# Light_Schematic.net
KiCad netlist of a schematic drawn in EAGLE
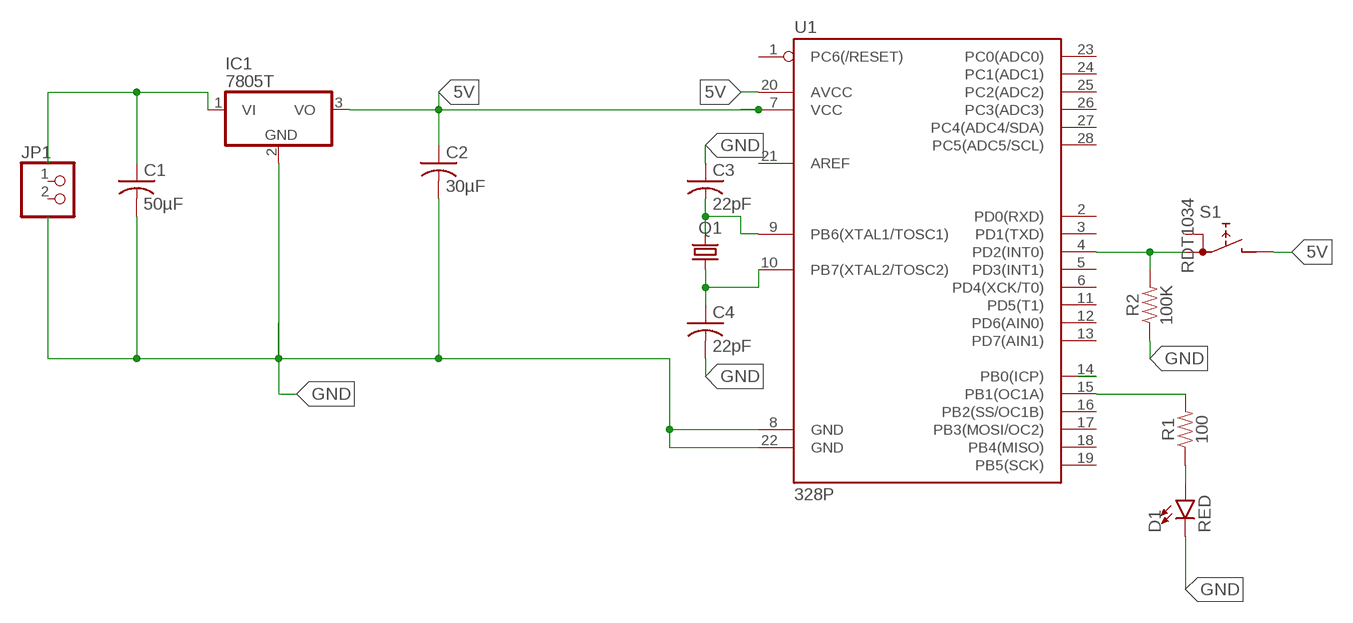
[diagram p0: schematic, sheet 1]

(export (version "E")
  (design (tool "Eeschema 10.0.6"))
  (components
    (comp (ref "C1")
      (value "50µF")
      (footprint "eagle-import:C0805")
      (libsource (lib "eagle-import") (part "C-USC0805"))
    )
    (comp (ref "C2")
      (value "30µF")
      (footprint "eagle-import:C0805")
      (libsource (lib "eagle-import") (part "C-USC0805"))
    )
    (comp (ref "C3")
      (value "22pF")
      (footprint "eagle-import:C0805")
      (libsource (lib "eagle-import") (part "C-USC0805"))
    )
    (comp (ref "C4")
      (value "22pF")
      (footprint "eagle-import:C0805")
      (libsource (lib "eagle-import") (part "C-USC0805"))
    )
    (comp (ref "D1")
      (value "RED")
      (footprint "eagle-import:LED-0603")
      (libsource (lib "eagle-import") (part "LED-RED0603"))
    )
    (comp (ref "IC1")
      (value "7805T")
      (footprint "eagle-import:TO220H")
      (libsource (lib "eagle-import") (part "78T05"))
    )
    (comp (ref "JP1")
      (value "PINHD-1X2")
      (footprint "eagle-import:1X02")
      (libsource (lib "eagle-import") (part "PINHD-1X2"))
    )
    (comp (ref "Q1")
      (value "CRYSTALHC49S")
      (footprint "eagle-import:HC49_S")
      (libsource (lib "eagle-import") (part "CRYSTALHC49S"))
    )
    (comp (ref "R1")
      (value "100")
      (footprint "eagle-import:0402")
      (libsource (lib "eagle-import") (part "100KOHM-0402-1/16W-1%"))
    )
    (comp (ref "R2")
      (value "100K")
      (footprint "eagle-import:0402")
      (libsource (lib "eagle-import") (part "100KOHM-0402-1/16W-1%"))
    )
    (comp (ref "S1")
      (value "RDT1034")
      (footprint "eagle-import:RDT1034")
      (libsource (lib "eagle-import") (part "RDT1034"))
    )
    (comp (ref "U1")
      (value "328P")
      (footprint "eagle-import:DIP28")
      (libsource (lib "eagle-import") (part "ATMEGA328P_PDIP"))
    )
  )
  (nets
    (net (code "1") (name "5V") (class "Default")
      (node (ref "C2") (pin "1") (pinfunction "1_1") (pintype "passive"))
      (node (ref "IC1") (pin "3") (pinfunction "VO_3") (pintype "passive"))
      (node (ref "S1") (pin "B") (pinfunction "B_B") (pintype "passive"))
      (node (ref "U1") (pin "20") (pinfunction "AVCC_20") (pintype "bidirectional"))
      (node (ref "U1") (pin "7") (pinfunction "VCC_7") (pintype "bidirectional"))
    )
    (net (code "2") (name "GND") (class "Default")
      (node (ref "C1") (pin "2") (pinfunction "2_2") (pintype "passive"))
      (node (ref "C2") (pin "2") (pinfunction "2_2") (pintype "passive"))
      (node (ref "C3") (pin "1") (pinfunction "1_1") (pintype "passive"))
      (node (ref "C4") (pin "2") (pinfunction "2_2") (pintype "passive"))
      (node (ref "D1") (pin "C") (pinfunction "C_C") (pintype "passive"))
      (node (ref "IC1") (pin "2") (pinfunction "GND_2") (pintype "passive"))
      (node (ref "R2") (pin "1") (pinfunction "1_1") (pintype "passive"))
      (node (ref "U1") (pin "22") (pinfunction "GND_22") (pintype "bidirectional"))
      (node (ref "U1") (pin "8") (pinfunction "GND_8") (pintype "bidirectional"))
    )
    (net (code "3") (name "Net-(D1-PadA)") (class "Default")
      (node (ref "D1") (pin "A") (pinfunction "A_A") (pintype "passive"))
      (node (ref "R1") (pin "1") (pinfunction "1_1") (pintype "passive"))
    )
    (net (code "4") (name "Net-(IC1-VI)") (class "Default")
      (node (ref "C1") (pin "1") (pinfunction "1_1") (pintype "passive"))
      (node (ref "IC1") (pin "1") (pinfunction "VI_1") (pintype "input"))
    )
    (net (code "5") (name "Net-(U1-PB1(OC1A))") (class "Default")
      (node (ref "R1") (pin "2") (pinfunction "2_2") (pintype "passive"))
      (node (ref "U1") (pin "15") (pinfunction "PB1(OC1A)_15") (pintype "bidirectional"))
    )
    (net (code "6") (name "Net-(U1-PB6(XTAL1{slash}TOSC1))") (class "Default")
      (node (ref "C3") (pin "2") (pinfunction "2_2") (pintype "passive"))
      (node (ref "Q1") (pin "2") (pinfunction "2_2") (pintype "passive"))
      (node (ref "U1") (pin "9") (pinfunction "PB6(XTAL1/TOSC1)_9") (pintype "bidirectional"))
    )
    (net (code "7") (name "Net-(U1-PB7(XTAL2{slash}TOSC2))") (class "Default")
      (node (ref "C4") (pin "1") (pinfunction "1_1") (pintype "passive"))
      (node (ref "Q1") (pin "1") (pinfunction "1_1") (pintype "passive"))
      (node (ref "U1") (pin "10") (pinfunction "PB7(XTAL2/TOSC2)_10") (pintype "bidirectional"))
    )
    (net (code "8") (name "Net-(U1-PD2(INT0))") (class "Default")
      (node (ref "R2") (pin "2") (pinfunction "2_2") (pintype "passive"))
      (node (ref "S1") (pin "A1") (pinfunction "A1_A1") (pintype "passive"))
      (node (ref "U1") (pin "4") (pinfunction "PD2(INT0)_4") (pintype "bidirectional"))
    )
    (net (code "9") (name "unconnected-(JP1-Pad1)") (class "Default")
      (node (ref "JP1") (pin "1") (pinfunction "1_1") (pintype "passive"))
    )
    (net (code "10") (name "unconnected-(JP1-Pad2)") (class "Default")
      (node (ref "JP1") (pin "2") (pinfunction "2_2") (pintype "passive"))
    )
    (net (code "11") (name "unconnected-(S1-PadA)") (class "Default")
      (node (ref "S1") (pin "A") (pinfunction "A_A") (pintype "passive"))
    )
    (net (code "12") (name "unconnected-(U1-AREF-Pad21)") (class "Default")
      (node (ref "U1") (pin "21") (pinfunction "AREF_21") (pintype "bidirectional"))
    )
    (net (code "13") (name "unconnected-(U1-PB0(ICP)-Pad14)") (class "Default")
      (node (ref "U1") (pin "14") (pinfunction "PB0(ICP)_14") (pintype "bidirectional"))
    )
    (net (code "14") (name "unconnected-(U1-PB2(SS{slash}OC1B)-Pad16)") (class "Default")
      (node (ref "U1") (pin "16") (pinfunction "PB2(SS/OC1B)_16") (pintype "bidirectional"))
    )
    (net (code "15") (name "unconnected-(U1-PB3(MOSI{slash}OC2)-Pad17)") (class "Default")
      (node (ref "U1") (pin "17") (pinfunction "PB3(MOSI/OC2)_17") (pintype "bidirectional"))
    )
    (net (code "16") (name "unconnected-(U1-PB4(MISO)-Pad18)") (class "Default")
      (node (ref "U1") (pin "18") (pinfunction "PB4(MISO)_18") (pintype "bidirectional"))
    )
    (net (code "17") (name "unconnected-(U1-PB5(SCK)-Pad19)") (class "Default")
      (node (ref "U1") (pin "19") (pinfunction "PB5(SCK)_19") (pintype "bidirectional"))
    )
    (net (code "18") (name "unconnected-(U1-PC0(ADC0)-Pad23)") (class "Default")
      (node (ref "U1") (pin "23") (pinfunction "PC0(ADC0)_23") (pintype "bidirectional"))
    )
    (net (code "19") (name "unconnected-(U1-PC1(ADC1)-Pad24)") (class "Default")
      (node (ref "U1") (pin "24") (pinfunction "PC1(ADC1)_24") (pintype "bidirectional"))
    )
    (net (code "20") (name "unconnected-(U1-PC2(ADC2)-Pad25)") (class "Default")
      (node (ref "U1") (pin "25") (pinfunction "PC2(ADC2)_25") (pintype "bidirectional"))
    )
    (net (code "21") (name "unconnected-(U1-PC3(ADC3)-Pad26)") (class "Default")
      (node (ref "U1") (pin "26") (pinfunction "PC3(ADC3)_26") (pintype "bidirectional"))
    )
    (net (code "22") (name "unconnected-(U1-PC4(ADC4{slash}SDA)-Pad27)") (class "Default")
      (node (ref "U1") (pin "27") (pinfunction "PC4(ADC4/SDA)_27") (pintype "bidirectional"))
    )
    (net (code "23") (name "unconnected-(U1-PC5(ADC5{slash}SCL)-Pad28)") (class "Default")
      (node (ref "U1") (pin "28") (pinfunction "PC5(ADC5/SCL)_28") (pintype "bidirectional"))
    )
    (net (code "24") (name "unconnected-(U1-PC6({slash}RESET)-Pad1)") (class "Default")
      (node (ref "U1") (pin "1") (pinfunction "PC6(/RESET)_1") (pintype "bidirectional"))
    )
    (net (code "25") (name "unconnected-(U1-PD0(RXD)-Pad2)") (class "Default")
      (node (ref "U1") (pin "2") (pinfunction "PD0(RXD)_2") (pintype "bidirectional"))
    )
    (net (code "26") (name "unconnected-(U1-PD1(TXD)-Pad3)") (class "Default")
      (node (ref "U1") (pin "3") (pinfunction "PD1(TXD)_3") (pintype "bidirectional"))
    )
    (net (code "27") (name "unconnected-(U1-PD3(INT1)-Pad5)") (class "Default")
      (node (ref "U1") (pin "5") (pinfunction "PD3(INT1)_5") (pintype "bidirectional"))
    )
    (net (code "28") (name "unconnected-(U1-PD4(XCK{slash}T0)-Pad6)") (class "Default")
      (node (ref "U1") (pin "6") (pinfunction "PD4(XCK/T0)_6") (pintype "bidirectional"))
    )
    (net (code "29") (name "unconnected-(U1-PD5(T1)-Pad11)") (class "Default")
      (node (ref "U1") (pin "11") (pinfunction "PD5(T1)_11") (pintype "bidirectional"))
    )
    (net (code "30") (name "unconnected-(U1-PD6(AIN0)-Pad12)") (class "Default")
      (node (ref "U1") (pin "12") (pinfunction "PD6(AIN0)_12") (pintype "bidirectional"))
    )
    (net (code "31") (name "unconnected-(U1-PD7(AIN1)-Pad13)") (class "Default")
      (node (ref "U1") (pin "13") (pinfunction "PD7(AIN1)_13") (pintype "bidirectional"))
    )
  )
)
